# Contactors.net
KiCad netlist of a schematic drawn in Altium Designer
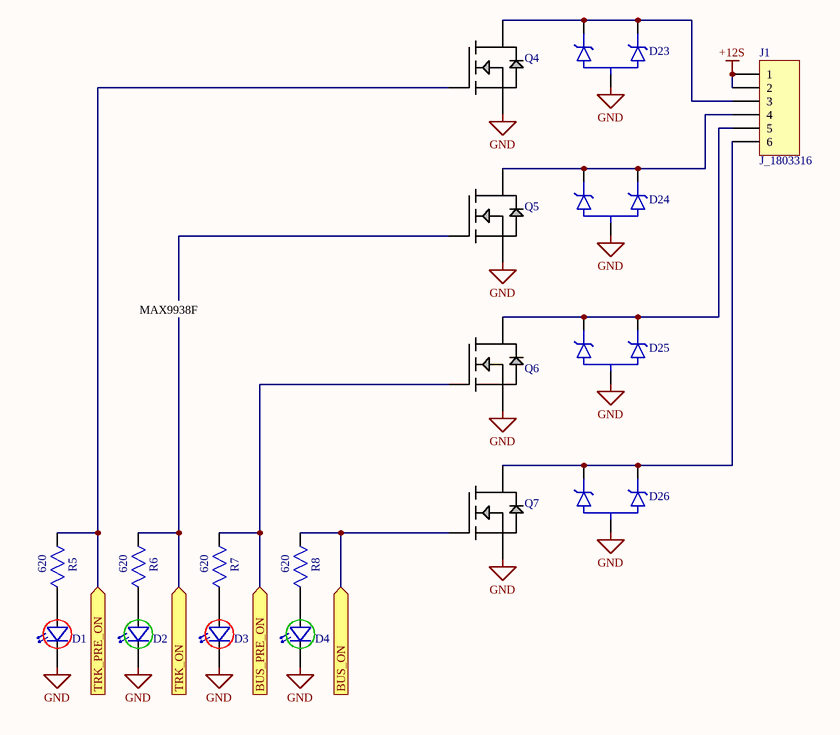
[diagram p0: Contactors.SchDoc]

(export (version "E")
  (design (tool "Eeschema 10.0.6"))
  (components
    (comp (ref "D1")
      (value "D_LED_0805_RED")
      (footprint "0805P_RED")
      (description "LED CHIPLED 645NM RED DIFF 0805")
      (fields (field (name "SVP CREATOR") "Jonathan Nutzmann"))
      (libsource (lib "c3_SchLib") (part "D_LED_0805_RED"))
    )
    (comp (ref "D2")
      (value "D_LED_0805_GREEN")
      (footprint "0805P_Green")
      (description "LED CHIPLED 570NM GREEN 0805 SMD")
      (fields
        (field (name "MANUFACTURER") "Osram Opto Semiconductors Inc")
        (field (name "SVP CREATOR") "Nate Bolyard")
        (field (name "SVP REVIEWER 1") "Trevtron")
      )
      (libsource (lib "c3_SchLib") (part "D_LED_0805_GREEN"))
    )
    (comp (ref "D3")
      (value "D_LED_0805_RED")
      (footprint "0805P_RED")
      (description "LED CHIPLED 645NM RED DIFF 0805")
      (fields (field (name "SVP CREATOR") "Jonathan Nutzmann"))
      (libsource (lib "c3_SchLib") (part "D_LED_0805_RED"))
    )
    (comp (ref "D4")
      (value "D_LED_0805_GREEN")
      (footprint "0805P_Green")
      (description "LED CHIPLED 570NM GREEN 0805 SMD")
      (fields
        (field (name "MANUFACTURER") "Osram Opto Semiconductors Inc")
        (field (name "SVP CREATOR") "Nate Bolyard")
        (field (name "SVP REVIEWER 1") "Trevtron")
      )
      (libsource (lib "c3_SchLib") (part "D_LED_0805_GREEN"))
    )
    (comp (ref "D23")
      (value "D_AZ23C36-TP")
      (footprint "SOT-23")
      (description "DIODE ZENER DUAL 36V SOT-23")
      (fields (field (name "MANUFACTURER") "Micro") (field (name "SVP CREATOR") "Jonathan Nutzmann"))
      (libsource (lib "c3_SchLib") (part "D_AZ23C36-TP"))
    )
    (comp (ref "D24")
      (value "D_AZ23C36-TP")
      (footprint "SOT-23")
      (description "DIODE ZENER DUAL 36V SOT-23")
      (fields (field (name "MANUFACTURER") "Micro") (field (name "SVP CREATOR") "Jonathan Nutzmann"))
      (libsource (lib "c3_SchLib") (part "D_AZ23C36-TP"))
    )
    (comp (ref "D25")
      (value "D_AZ23C36-TP")
      (footprint "SOT-23")
      (description "DIODE ZENER DUAL 36V SOT-23")
      (fields (field (name "MANUFACTURER") "Micro") (field (name "SVP CREATOR") "Jonathan Nutzmann"))
      (libsource (lib "c3_SchLib") (part "D_AZ23C36-TP"))
    )
    (comp (ref "D26")
      (value "D_AZ23C36-TP")
      (footprint "SOT-23")
      (description "DIODE ZENER DUAL 36V SOT-23")
      (fields (field (name "MANUFACTURER") "Micro") (field (name "SVP CREATOR") "Jonathan Nutzmann"))
      (libsource (lib "c3_SchLib") (part "D_AZ23C36-TP"))
    )
    (comp (ref "J1")
      (value "J_1803316")
      (footprint "1844252")
      (description "CONN HEADER RT ANG 6POS 3.81MM")
      (fields (field (name "MANUFACTURER") "Phoenix Contact"))
      (libsource (lib "Nutz") (part "J_1803316"))
    )
    (comp (ref "Q4")
      (value "RK7002BT116")
      (footprint "SOT-23")
      (description "MOSFET N-CH 60V 250MA SOT-23")
      (fields
        (field (name "MANUFACTURER") "Rohm Semiconductor")
        (field (name "SVP CREATOR") "Jonathan Nutzmann")
      )
      (libsource (lib "c3_SchLib") (part "Q_N_60V_250MA_SOT23"))
    )
    (comp (ref "Q5")
      (value "RK7002BT116")
      (footprint "SOT-23")
      (description "MOSFET N-CH 60V 250MA SOT-23")
      (fields
        (field (name "MANUFACTURER") "Rohm Semiconductor")
        (field (name "SVP CREATOR") "Jonathan Nutzmann")
      )
      (libsource (lib "c3_SchLib") (part "Q_N_60V_250MA_SOT23"))
    )
    (comp (ref "Q6")
      (value "RK7002BT116")
      (footprint "SOT-23")
      (description "MOSFET N-CH 60V 250MA SOT-23")
      (fields
        (field (name "MANUFACTURER") "Rohm Semiconductor")
        (field (name "SVP CREATOR") "Jonathan Nutzmann")
      )
      (libsource (lib "c3_SchLib") (part "Q_N_60V_250MA_SOT23"))
    )
    (comp (ref "Q7")
      (value "RK7002BT116")
      (footprint "SOT-23")
      (description "MOSFET N-CH 60V 250MA SOT-23")
      (fields
        (field (name "MANUFACTURER") "Rohm Semiconductor")
        (field (name "SVP CREATOR") "Jonathan Nutzmann")
      )
      (libsource (lib "c3_SchLib") (part "Q_N_60V_250MA_SOT23"))
    )
    (comp (ref "R5")
      (value "620")
      (footprint "0603_res")
      (description "RES 620 OHM 1/8W 1% 0603 SMD")
      (fields (field (name "Comment") "R_0805_620_1%") (field (name "SVP CREATOR") "Jonathan Nutzmann"))
      (libsource (lib "c3_SchLib") (part "R_0805_620_1%"))
    )
    (comp (ref "R6")
      (value "620")
      (footprint "0603_res")
      (description "RES 620 OHM 1/8W 1% 0603 SMD")
      (fields (field (name "Comment") "R_0805_620_1%") (field (name "SVP CREATOR") "Jonathan Nutzmann"))
      (libsource (lib "c3_SchLib") (part "R_0805_620_1%"))
    )
    (comp (ref "R7")
      (value "620")
      (footprint "0603_res")
      (description "RES 620 OHM 1/8W 1% 0603 SMD")
      (fields (field (name "Comment") "R_0805_620_1%") (field (name "SVP CREATOR") "Jonathan Nutzmann"))
      (libsource (lib "c3_SchLib") (part "R_0805_620_1%"))
    )
    (comp (ref "R8")
      (value "620")
      (footprint "0603_res")
      (description "RES 620 OHM 1/8W 1% 0603 SMD")
      (fields (field (name "Comment") "R_0805_620_1%") (field (name "SVP CREATOR") "Jonathan Nutzmann"))
      (libsource (lib "c3_SchLib") (part "R_0805_620_1%"))
    )
  )
  (nets
    (net (code "1") (name "+12S") (class "Default")
      (node (ref "J1") (pin "1") (pinfunction "1_1") (pintype "passive"))
      (node (ref "J1") (pin "2") (pinfunction "2_2") (pintype "passive"))
    )
    (net (code "2") (name "/BUS_ON") (class "Default")
      (node (ref "Q7") (pin "1") (pinfunction "GATE_1") (pintype "passive"))
      (node (ref "R8") (pin "2") (pinfunction "2_2") (pintype "passive"))
    )
    (net (code "3") (name "/BUS_PRE_ON") (class "Default")
      (node (ref "Q6") (pin "1") (pinfunction "GATE_1") (pintype "passive"))
      (node (ref "R7") (pin "2") (pinfunction "2_2") (pintype "passive"))
    )
    (net (code "4") (name "/TRK_ON") (class "Default")
      (node (ref "Q5") (pin "1") (pinfunction "GATE_1") (pintype "passive"))
      (node (ref "R6") (pin "2") (pinfunction "2_2") (pintype "passive"))
    )
    (net (code "5") (name "/TRK_PRE_ON") (class "Default")
      (node (ref "Q4") (pin "1") (pinfunction "GATE_1") (pintype "passive"))
      (node (ref "R5") (pin "2") (pinfunction "2_2") (pintype "passive"))
    )
    (net (code "6") (name "GND") (class "Default")
      (node (ref "D1") (pin "1") (pinfunction "Cathode_1") (pintype "passive"))
      (node (ref "D2") (pin "1") (pinfunction "Cathode_1") (pintype "passive"))
      (node (ref "D23") (pin "3") (pinfunction "ANODE_3") (pintype "passive"))
      (node (ref "D24") (pin "3") (pinfunction "ANODE_3") (pintype "passive"))
      (node (ref "D25") (pin "3") (pinfunction "ANODE_3") (pintype "passive"))
      (node (ref "D26") (pin "3") (pinfunction "ANODE_3") (pintype "passive"))
      (node (ref "D3") (pin "1") (pinfunction "Cathode_1") (pintype "passive"))
      (node (ref "D4") (pin "1") (pinfunction "Cathode_1") (pintype "passive"))
      (node (ref "Q4") (pin "2") (pinfunction "SOURCE_2") (pintype "passive"))
      (node (ref "Q5") (pin "2") (pinfunction "SOURCE_2") (pintype "passive"))
      (node (ref "Q6") (pin "2") (pinfunction "SOURCE_2") (pintype "passive"))
      (node (ref "Q7") (pin "2") (pinfunction "SOURCE_2") (pintype "passive"))
    )
    (net (code "7") (name "Net-(D1-Anode)") (class "Default")
      (node (ref "D1") (pin "2") (pinfunction "Anode_2") (pintype "passive"))
      (node (ref "R5") (pin "1") (pinfunction "1_1") (pintype "passive"))
    )
    (net (code "8") (name "Net-(D2-Anode)") (class "Default")
      (node (ref "D2") (pin "2") (pinfunction "Anode_2") (pintype "passive"))
      (node (ref "R6") (pin "1") (pinfunction "1_1") (pintype "passive"))
    )
    (net (code "9") (name "Net-(D3-Anode)") (class "Default")
      (node (ref "D3") (pin "2") (pinfunction "Anode_2") (pintype "passive"))
      (node (ref "R7") (pin "1") (pinfunction "1_1") (pintype "passive"))
    )
    (net (code "10") (name "Net-(D4-Anode)") (class "Default")
      (node (ref "D4") (pin "2") (pinfunction "Anode_2") (pintype "passive"))
      (node (ref "R8") (pin "1") (pinfunction "1_1") (pintype "passive"))
    )
    (net (code "11") (name "Net-(D23-CATHODE_1)") (class "Default")
      (node (ref "D23") (pin "1") (pinfunction "CATHODE_1_1") (pintype "passive"))
      (node (ref "D23") (pin "2") (pinfunction "CATHODE_2_2") (pintype "passive"))
      (node (ref "J1") (pin "3") (pinfunction "3_3") (pintype "passive"))
      (node (ref "Q4") (pin "3") (pinfunction "DRAIN_3") (pintype "passive"))
    )
    (net (code "12") (name "Net-(D24-CATHODE_1)") (class "Default")
      (node (ref "D24") (pin "1") (pinfunction "CATHODE_1_1") (pintype "passive"))
      (node (ref "D24") (pin "2") (pinfunction "CATHODE_2_2") (pintype "passive"))
      (node (ref "J1") (pin "4") (pinfunction "4_4") (pintype "passive"))
      (node (ref "Q5") (pin "3") (pinfunction "DRAIN_3") (pintype "passive"))
    )
    (net (code "13") (name "Net-(D25-CATHODE_1)") (class "Default")
      (node (ref "D25") (pin "1") (pinfunction "CATHODE_1_1") (pintype "passive"))
      (node (ref "D25") (pin "2") (pinfunction "CATHODE_2_2") (pintype "passive"))
      (node (ref "J1") (pin "5") (pinfunction "5_5") (pintype "passive"))
      (node (ref "Q6") (pin "3") (pinfunction "DRAIN_3") (pintype "passive"))
    )
    (net (code "14") (name "Net-(D26-CATHODE_1)") (class "Default")
      (node (ref "D26") (pin "1") (pinfunction "CATHODE_1_1") (pintype "passive"))
      (node (ref "D26") (pin "2") (pinfunction "CATHODE_2_2") (pintype "passive"))
      (node (ref "J1") (pin "6") (pinfunction "6_6") (pintype "passive"))
      (node (ref "Q7") (pin "3") (pinfunction "DRAIN_3") (pintype "passive"))
    )
  )
)
